# MINIM_PCB.net
KiCad netlist of a schematic drawn in EAGLE
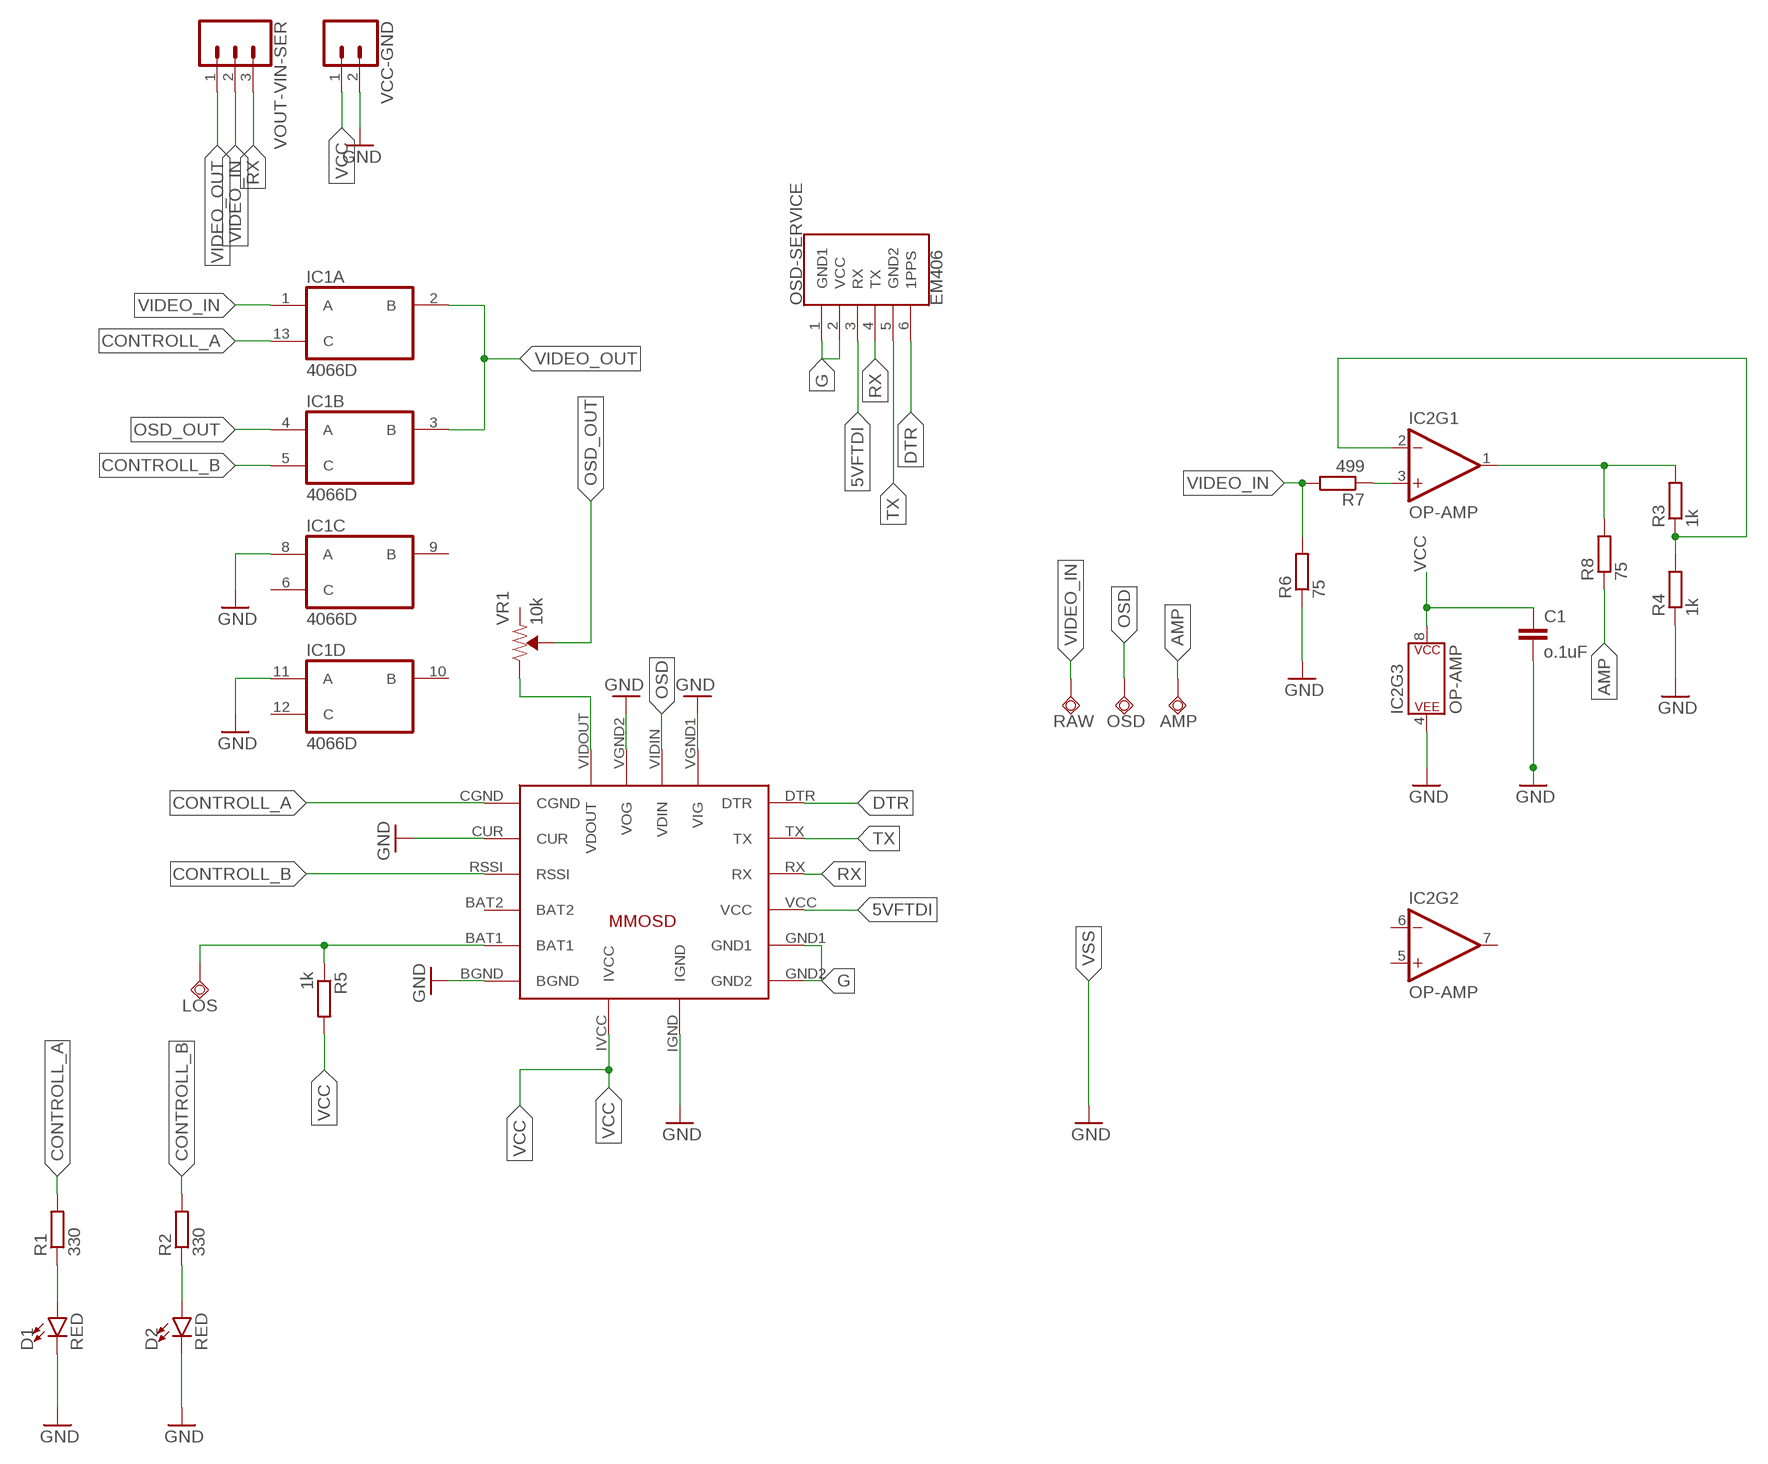
[diagram p0: schematic, sheet 1]

(export (version "E")
  (design (tool "Eeschema 10.0.6"))
  (components
    (comp (ref "AMP")
      (value "TPSQTP13SQ")
      (footprint "eagle-import:TP13SQ")
      (libsource (lib "eagle-import") (part "TPSQTP13SQ"))
    )
    (comp (ref "C1")
      (value "o.1uF")
      (footprint "eagle-import:C0603K")
      (libsource (lib "eagle-import") (part "C-EUC0603K"))
    )
    (comp (ref "D1")
      (value "RED")
      (footprint "eagle-import:LED-1206")
      (libsource (lib "eagle-import") (part "LED-RED1206"))
    )
    (comp (ref "D2")
      (value "RED")
      (footprint "eagle-import:LED-1206")
      (libsource (lib "eagle-import") (part "LED-RED1206"))
    )
    (comp (ref "IC1")
      (value "4066D")
      (footprint "eagle-import:SO14")
      (libsource (lib "eagle-import") (part "4066D"))
    )
    (comp (ref "IC2")
      (value "OP-AMP")
      (footprint "eagle-import:SO08")
      (libsource (lib "eagle-import") (part "OPAMP-DUALU"))
    )
    (comp (ref "LOS")
      (value "TPSQTP13SQ")
      (footprint "eagle-import:TP13SQ")
      (libsource (lib "eagle-import") (part "TPSQTP13SQ"))
    )
    (comp (ref "MINIMOSD")
      (value "MICROMINIMOSDPWR")
      (footprint "eagle-import:MMOSDNVDVID")
      (libsource (lib "eagle-import") (part "MICROMINIMOSDPWR"))
    )
    (comp (ref "OSD")
      (value "TPSQTP13SQ")
      (footprint "eagle-import:TP13SQ")
      (libsource (lib "eagle-import") (part "TPSQTP13SQ"))
    )
    (comp (ref "OSD-SERVICE")
      (value "EM406")
      (footprint "eagle-import:1X06-1MM")
      (libsource (lib "eagle-import") (part "EM406"))
    )
    (comp (ref "R1")
      (value "330")
      (footprint "eagle-import:R0603")
      (libsource (lib "eagle-import") (part "R-EU_R0603"))
    )
    (comp (ref "R2")
      (value "330")
      (footprint "eagle-import:R0603")
      (libsource (lib "eagle-import") (part "R-EU_R0603"))
    )
    (comp (ref "R3")
      (value "1k")
      (footprint "eagle-import:R0603")
      (libsource (lib "eagle-import") (part "R-EU_R0603"))
    )
    (comp (ref "R4")
      (value "1k")
      (footprint "eagle-import:R0603")
      (libsource (lib "eagle-import") (part "R-EU_R0603"))
    )
    (comp (ref "R5")
      (value "1k")
      (footprint "eagle-import:R0603")
      (libsource (lib "eagle-import") (part "R-EU_R0603"))
    )
    (comp (ref "R6")
      (value "75")
      (footprint "eagle-import:R0603")
      (libsource (lib "eagle-import") (part "R-EU_R0603"))
    )
    (comp (ref "R7")
      (value "499")
      (footprint "eagle-import:R0603")
      (libsource (lib "eagle-import") (part "R-EU_R0603"))
    )
    (comp (ref "R8")
      (value "75")
      (footprint "eagle-import:R0603")
      (libsource (lib "eagle-import") (part "R-EU_R0603"))
    )
    (comp (ref "RAW")
      (value "TPSQTP13SQ")
      (footprint "eagle-import:TP13SQ")
      (libsource (lib "eagle-import") (part "TPSQTP13SQ"))
    )
    (comp (ref "VCC-GND")
      (value "CONN_02")
      (footprint "eagle-import:1X02")
      (libsource (lib "eagle-import") (part "CONN_02"))
    )
    (comp (ref "VOUT-VIN-SER")
      (value "CONN_03")
      (footprint "eagle-import:1X03")
      (libsource (lib "eagle-import") (part "CONN_03"))
    )
    (comp (ref "VR1")
      (value "10k")
      (footprint "eagle-import:TRIMPOT-SMD-3MM-CLOSED")
      (libsource (lib "eagle-import") (part "TRIMPOT-SMD-3MM-CLOSED-1/8W-20%"))
    )
  )
  (nets
    (net (code "1") (name "/BAT2") (class "Default")
      (node (ref "MINIMOSD") (pin "BAT2") (pinfunction "BAT2_BAT2") (pintype "power_in"))
    )
    (net (code "2") (name "5VFTDI") (class "Default")
      (node (ref "MINIMOSD") (pin "VCC") (pinfunction "VCC_VCC") (pintype "power_in"))
      (node (ref "OSD-SERVICE") (pin "3") (pinfunction "RX_3") (pintype "bidirectional"))
    )
    (net (code "3") (name "AMP") (class "Default")
      (node (ref "AMP") (pin "TP") (pinfunction "TP_TP") (pintype "input"))
      (node (ref "R8") (pin "1") (pinfunction "1_1") (pintype "passive"))
    )
    (net (code "4") (name "CONTROLL_A") (class "Default")
      (node (ref "IC1") (pin "13") (pinfunction "C_13") (pintype "input"))
      (node (ref "MINIMOSD") (pin "CGND") (pinfunction "CGND_CGND") (pintype "power_in"))
      (node (ref "R1") (pin "2") (pinfunction "2_2") (pintype "passive"))
    )
    (net (code "5") (name "CONTROLL_B") (class "Default")
      (node (ref "IC1") (pin "5") (pinfunction "C_5") (pintype "input"))
      (node (ref "MINIMOSD") (pin "RSSI") (pinfunction "RSSI_RSSI") (pintype "bidirectional"))
      (node (ref "R2") (pin "2") (pinfunction "2_2") (pintype "passive"))
    )
    (net (code "6") (name "DTR") (class "Default")
      (node (ref "MINIMOSD") (pin "DTR") (pinfunction "DTR_DTR") (pintype "bidirectional"))
      (node (ref "OSD-SERVICE") (pin "6") (pinfunction "1PPS_6") (pintype "bidirectional"))
    )
    (net (code "7") (name "G") (class "Default")
      (node (ref "MINIMOSD") (pin "GND1") (pinfunction "GND1_GND1") (pintype "power_in"))
      (node (ref "MINIMOSD") (pin "GND2") (pinfunction "GND2_GND2") (pintype "power_in"))
      (node (ref "OSD-SERVICE") (pin "1") (pinfunction "GND1_1") (pintype "bidirectional"))
      (node (ref "OSD-SERVICE") (pin "2") (pinfunction "VCC_2") (pintype "bidirectional"))
    )
    (net (code "8") (name "Net-(D1-PadA)") (class "Default")
      (node (ref "D1") (pin "A") (pinfunction "A_A") (pintype "passive"))
      (node (ref "R1") (pin "1") (pinfunction "1_1") (pintype "passive"))
    )
    (net (code "9") (name "Net-(D2-PadA)") (class "Default")
      (node (ref "D2") (pin "A") (pinfunction "A_A") (pintype "passive"))
      (node (ref "R2") (pin "1") (pinfunction "1_1") (pintype "passive"))
    )
    (net (code "10") (name "Net-(IC2A-+IN)") (class "Default")
      (node (ref "IC2") (pin "3") (pinfunction "+IN_3") (pintype "input"))
      (node (ref "R7") (pin "1") (pinfunction "1_1") (pintype "passive"))
    )
    (net (code "11") (name "Net-(IC2A--IN)") (class "Default")
      (node (ref "IC2") (pin "2") (pinfunction "-IN_2") (pintype "input"))
      (node (ref "R3") (pin "1") (pinfunction "1_1") (pintype "passive"))
      (node (ref "R4") (pin "2") (pinfunction "2_2") (pintype "passive"))
    )
    (net (code "12") (name "Net-(IC2A-OUT)") (class "Default")
      (node (ref "IC2") (pin "1") (pinfunction "OUT_1") (pintype "output"))
      (node (ref "R3") (pin "2") (pinfunction "2_2") (pintype "passive"))
      (node (ref "R8") (pin "2") (pinfunction "2_2") (pintype "passive"))
    )
    (net (code "13") (name "Net-(LOS-PadTP)") (class "Default")
      (node (ref "LOS") (pin "TP") (pinfunction "TP_TP") (pintype "input"))
      (node (ref "MINIMOSD") (pin "BAT1") (pinfunction "BAT1_BAT1") (pintype "power_in"))
      (node (ref "R5") (pin "1") (pinfunction "1_1") (pintype "passive"))
    )
    (net (code "14") (name "Net-(MINIMOSD-VDOUT)") (class "Default")
      (node (ref "MINIMOSD") (pin "VIDOUT") (pinfunction "VDOUT_VIDOUT") (pintype "output"))
      (node (ref "VR1") (pin "3") (pinfunction "CW_3") (pintype "passive"))
    )
    (net (code "15") (name "OSD") (class "Default")
      (node (ref "MINIMOSD") (pin "VIDIN") (pinfunction "VDIN_VIDIN") (pintype "input"))
      (node (ref "OSD") (pin "TP") (pinfunction "TP_TP") (pintype "input"))
    )
    (net (code "16") (name "OSD_OUT") (class "Default")
      (node (ref "IC1") (pin "4") (pinfunction "A_4") (pintype "tri_state"))
      (node (ref "VR1") (pin "2") (pinfunction "WIPER_2") (pintype "passive"))
    )
    (net (code "17") (name "RX") (class "Default")
      (node (ref "MINIMOSD") (pin "RX") (pinfunction "RX_RX") (pintype "input"))
      (node (ref "OSD-SERVICE") (pin "4") (pinfunction "TX_4") (pintype "bidirectional"))
      (node (ref "VOUT-VIN-SER") (pin "3") (pinfunction "3_3") (pintype "passive"))
    )
    (net (code "18") (name "TX") (class "Default")
      (node (ref "MINIMOSD") (pin "TX") (pinfunction "TX_TX") (pintype "output"))
      (node (ref "OSD-SERVICE") (pin "5") (pinfunction "GND2_5") (pintype "bidirectional"))
    )
    (net (code "19") (name "VCC") (class "Default")
      (node (ref "C1") (pin "1") (pinfunction "1_1") (pintype "passive"))
      (node (ref "IC2") (pin "8") (pinfunction "P$V+_8") (pintype "bidirectional"))
      (node (ref "MINIMOSD") (pin "IVCC") (pinfunction "IVCC_IVCC") (pintype "power_in"))
      (node (ref "R5") (pin "2") (pinfunction "2_2") (pintype "passive"))
      (node (ref "VCC-GND") (pin "1") (pinfunction "1_1") (pintype "passive"))
    )
    (net (code "20") (name "VIDEO_IN") (class "Default")
      (node (ref "IC1") (pin "1") (pinfunction "A_1") (pintype "tri_state"))
      (node (ref "R6") (pin "2") (pinfunction "2_2") (pintype "passive"))
      (node (ref "R7") (pin "2") (pinfunction "2_2") (pintype "passive"))
      (node (ref "RAW") (pin "TP") (pinfunction "TP_TP") (pintype "input"))
      (node (ref "VOUT-VIN-SER") (pin "2") (pinfunction "2_2") (pintype "passive"))
    )
    (net (code "21") (name "VIDEO_OUT") (class "Default")
      (node (ref "IC1") (pin "2") (pinfunction "B_2") (pintype "tri_state"))
      (node (ref "IC1") (pin "3") (pinfunction "B_3") (pintype "tri_state"))
      (node (ref "VOUT-VIN-SER") (pin "1") (pinfunction "1_1") (pintype "passive"))
    )
    (net (code "22") (name "VSS") (class "Default")
      (node (ref "C1") (pin "2") (pinfunction "2_2") (pintype "passive"))
      (node (ref "D1") (pin "C") (pinfunction "C_C") (pintype "passive"))
      (node (ref "D2") (pin "C") (pinfunction "C_C") (pintype "passive"))
      (node (ref "IC1") (pin "11") (pinfunction "A_11") (pintype "tri_state"))
      (node (ref "IC1") (pin "8") (pinfunction "A_8") (pintype "tri_state"))
      (node (ref "IC2") (pin "4") (pinfunction "P$V-_4") (pintype "bidirectional"))
      (node (ref "MINIMOSD") (pin "BGND") (pinfunction "BGND_BGND") (pintype "power_in"))
      (node (ref "MINIMOSD") (pin "CUR") (pinfunction "CUR_CUR") (pintype "bidirectional"))
      (node (ref "MINIMOSD") (pin "IGND") (pinfunction "IGND_IGND") (pintype "power_in"))
      (node (ref "MINIMOSD") (pin "VGND1") (pinfunction "VIG_VGND1") (pintype "input"))
      (node (ref "MINIMOSD") (pin "VGND2") (pinfunction "VOG_VGND2") (pintype "output"))
      (node (ref "R4") (pin "1") (pinfunction "1_1") (pintype "passive"))
      (node (ref "R6") (pin "1") (pinfunction "1_1") (pintype "passive"))
      (node (ref "VCC-GND") (pin "2") (pinfunction "2_2") (pintype "passive"))
    )
    (net (code "23") (name "unconnected-(IC1C-B-Pad9)") (class "Default")
      (node (ref "IC1") (pin "9") (pinfunction "B_9") (pintype "tri_state"))
    )
    (net (code "24") (name "unconnected-(IC1C-C-Pad6)") (class "Default")
      (node (ref "IC1") (pin "6") (pinfunction "C_6") (pintype "input"))
    )
    (net (code "25") (name "unconnected-(IC1D-B-Pad10)") (class "Default")
      (node (ref "IC1") (pin "10") (pinfunction "B_10") (pintype "tri_state"))
    )
    (net (code "26") (name "unconnected-(IC1D-C-Pad12)") (class "Default")
      (node (ref "IC1") (pin "12") (pinfunction "C_12") (pintype "input"))
    )
    (net (code "27") (name "unconnected-(IC2B-+IN-Pad5)") (class "Default")
      (node (ref "IC2") (pin "5") (pinfunction "+IN_5") (pintype "input"))
    )
    (net (code "28") (name "unconnected-(IC2B--IN-Pad6)") (class "Default")
      (node (ref "IC2") (pin "6") (pinfunction "-IN_6") (pintype "input"))
    )
    (net (code "29") (name "unconnected-(IC2B-OUT-Pad7)") (class "Default")
      (node (ref "IC2") (pin "7") (pinfunction "OUT_7") (pintype "output"))
    )
    (net (code "30") (name "unconnected-(VR1-CCW-Pad1)") (class "Default")
      (node (ref "VR1") (pin "1") (pinfunction "CCW_1") (pintype "passive"))
    )
  )
)
